# Switch.net
KiCad netlist of a schematic drawn in Altium Designer
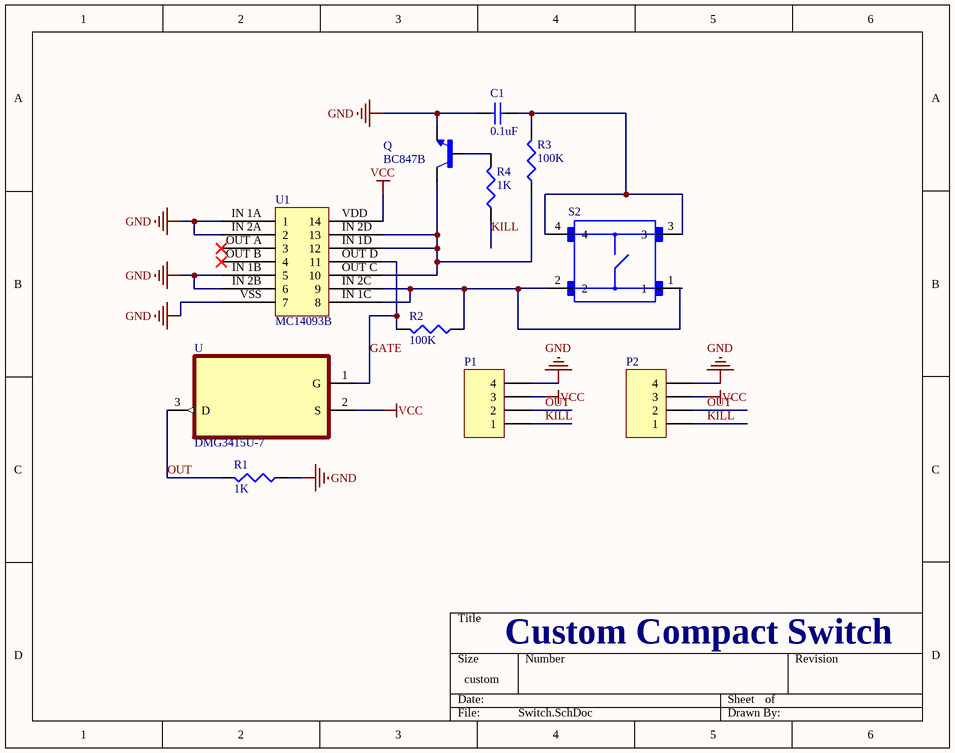
[diagram p0: Switch.SchDoc]

(export (version "E")
  (design (tool "Eeschema 10.0.6"))
  (components
    (comp (ref "C1")
      (value "0.1uF")
      (footprint "C0805")
      (description "Capacitor (Semiconductor SIM Model)")
      (fields (field (name "Comment") "Cap Semi") (field (name "PUBLISHER") "Altium Limited"))
      (libsource (lib "Miscellaneous Devices") (part "Cap Semi"))
    )
    (comp (ref "P1")
      (value "Header 4")
      (footprint "HDR1X4")
      (description "Header, 4-Pin")
      (fields (field (name "PUBLISHER") "Altium Limited"))
      (libsource (lib "Miscellaneous Connectors") (part "Header 4"))
    )
    (comp (ref "P2")
      (value "Header 4")
      (footprint "HDR1X4")
      (description "Header, 4-Pin")
      (fields (field (name "PUBLISHER") "Altium Limited"))
      (libsource (lib "Miscellaneous Connectors") (part "Header 4"))
    )
    (comp (ref "Q")
      (value "BC847B")
      (footprint "SOT100P230X110-3N")
      (description "Bipolar (BJT) Transistor NPN 45V 100mA 100MHz 150mW Surface Mount SOT-523")
      (fields (field (name "MF") "STMicroelectronics"))
      (libsource (lib "BC847B") (part "BC847B"))
    )
    (comp (ref "R1")
      (value "1K")
      (footprint "6-0805_N")
      (description "Resistor")
      (fields (field (name "Comment") "Res3") (field (name "PUBLISHER") "Altium Limited"))
      (libsource (lib "Miscellaneous Devices") (part "Res3"))
    )
    (comp (ref "R2")
      (value "100K")
      (footprint "6-0805_N")
      (description "Resistor")
      (fields (field (name "Comment") "Res3") (field (name "PUBLISHER") "Altium Limited"))
      (libsource (lib "Miscellaneous Devices") (part "Res3"))
    )
    (comp (ref "R3")
      (value "100K")
      (footprint "6-0805_N")
      (description "Resistor")
      (fields (field (name "Comment") "Res3") (field (name "PUBLISHER") "Altium Limited"))
      (libsource (lib "Miscellaneous Devices") (part "Res3"))
    )
    (comp (ref "R4")
      (value "1K")
      (footprint "6-0805_N")
      (description "Resistor")
      (fields (field (name "Comment") "Res3") (field (name "PUBLISHER") "Altium Limited"))
      (libsource (lib "Miscellaneous Devices") (part "Res3"))
    )
    (comp (ref "S2")
      (value "B3F-1000")
      (footprint "B3F4050")
      (description "Switch, FLUX TIGHT MECHANICAL KEYSwitch, , 50MA@24VDC, NO GROUND TERM., FLAT PLUNG")
      (fields (field (name "MF") "{'manufacturer': u'Omron'}"))
      (libsource (lib "*") (part "B3F-1000"))
    )
    (comp (ref "U")
      (value "DMG3415U-7")
      (footprint "SOT95P240X105-3N")
      (description "P-Channel 20V 4A _Ta_ 900mW _Ta_ Surface Mount SOT-23-3")
      (fields (field (name "MF") "Diodes Inc."))
      (libsource (lib "DMG3415U") (part "DMG3415U-7"))
    )
    (comp (ref "U1")
      (value "MC14093B")
      (footprint "SOP127P600X175-14N")
      (description "Quad 2-Input “NAND\"  Schmitt Trigger")
      (libsource (lib "MC14093B") (part "MC14093B"))
    )
  )
  (nets
    (net (code "1") (name "/GATE") (class "Default")
      (node (ref "R2") (pin "2") (pinfunction "2_2") (pintype "passive"))
      (node (ref "U") (pin "1") (pinfunction "G_1") (pintype "power_in"))
      (node (ref "U1") (pin "OUT_D") (pinfunction "11_OUT_D") (pintype "passive"))
    )
    (net (code "2") (name "/KILL") (class "Default")
      (node (ref "P1") (pin "1") (pinfunction "1_1") (pintype "passive"))
      (node (ref "P2") (pin "1") (pinfunction "1_1") (pintype "passive"))
      (node (ref "R4") (pin "1") (pinfunction "1_1") (pintype "passive"))
    )
    (net (code "3") (name "/OUT") (class "Default")
      (node (ref "P1") (pin "2") (pinfunction "2_2") (pintype "passive"))
      (node (ref "P2") (pin "2") (pinfunction "2_2") (pintype "passive"))
      (node (ref "R1") (pin "2") (pinfunction "2_2") (pintype "passive"))
      (node (ref "U") (pin "3") (pinfunction "D_3") (pintype "output"))
    )
    (net (code "4") (name "GND") (class "Default")
      (node (ref "C1") (pin "1") (pinfunction "1_1") (pintype "passive"))
      (node (ref "P1") (pin "4") (pinfunction "4_4") (pintype "passive"))
      (node (ref "P2") (pin "4") (pinfunction "4_4") (pintype "passive"))
      (node (ref "Q") (pin "2") (pinfunction "E_2") (pintype "passive"))
      (node (ref "R1") (pin "1") (pinfunction "1_1") (pintype "passive"))
      (node (ref "U1") (pin "IN_1A") (pinfunction "1_IN_1A") (pintype "passive"))
      (node (ref "U1") (pin "IN_1B") (pinfunction "5_IN_1B") (pintype "passive"))
      (node (ref "U1") (pin "IN_2A") (pinfunction "2_IN_2A") (pintype "passive"))
      (node (ref "U1") (pin "IN_2B") (pinfunction "6_IN_2B") (pintype "passive"))
      (node (ref "U1") (pin "VSS") (pinfunction "7_VSS") (pintype "passive"))
    )
    (net (code "5") (name "Net-(C1-Pad2)") (class "Default")
      (node (ref "C1") (pin "2") (pinfunction "2_2") (pintype "passive"))
      (node (ref "R3") (pin "2") (pinfunction "2_2") (pintype "passive"))
      (node (ref "S2") (pin "3") (pinfunction "3_3") (pintype "passive"))
      (node (ref "S2") (pin "4") (pinfunction "4_4") (pintype "passive"))
    )
    (net (code "6") (name "Net-(Q-B)") (class "Default")
      (node (ref "Q") (pin "1") (pinfunction "B_1") (pintype "passive"))
      (node (ref "R4") (pin "2") (pinfunction "2_2") (pintype "passive"))
    )
    (net (code "7") (name "Net-(Q-C)") (class "Default")
      (node (ref "Q") (pin "3") (pinfunction "C_3") (pintype "passive"))
      (node (ref "R3") (pin "1") (pinfunction "1_1") (pintype "passive"))
      (node (ref "U1") (pin "IN_1D") (pinfunction "12_IN_1D") (pintype "passive"))
      (node (ref "U1") (pin "IN_2D") (pinfunction "13_IN_2D") (pintype "passive"))
      (node (ref "U1") (pin "OUT_C") (pinfunction "10_OUT_C") (pintype "passive"))
    )
    (net (code "8") (name "Net-(U1-8)") (class "Default")
      (node (ref "R2") (pin "1") (pinfunction "1_1") (pintype "passive"))
      (node (ref "S2") (pin "1") (pinfunction "1_1") (pintype "passive"))
      (node (ref "S2") (pin "2") (pinfunction "2_2") (pintype "passive"))
      (node (ref "U1") (pin "IN_1C") (pinfunction "8_IN_1C") (pintype "passive"))
      (node (ref "U1") (pin "IN_2C") (pinfunction "9_IN_2C") (pintype "passive"))
    )
    (net (code "9") (name "VCC") (class "Default")
      (node (ref "P1") (pin "3") (pinfunction "3_3") (pintype "passive"))
      (node (ref "P2") (pin "3") (pinfunction "3_3") (pintype "passive"))
      (node (ref "U") (pin "2") (pinfunction "S_2") (pintype "passive"))
      (node (ref "U1") (pin "VDD") (pinfunction "14_VDD") (pintype "passive"))
    )
    (net (code "10") (name "unconnected-(U1-3-PadOUT_A)") (class "Default")
      (node (ref "U1") (pin "OUT_A") (pinfunction "3_OUT_A") (pintype "passive+no_connect"))
    )
    (net (code "11") (name "unconnected-(U1-4-PadOUT_B)") (class "Default")
      (node (ref "U1") (pin "OUT_B") (pinfunction "4_OUT_B") (pintype "passive+no_connect"))
    )
  )
)
